# Prototype_Schematic.net
KiCad netlist of a schematic drawn in EAGLE
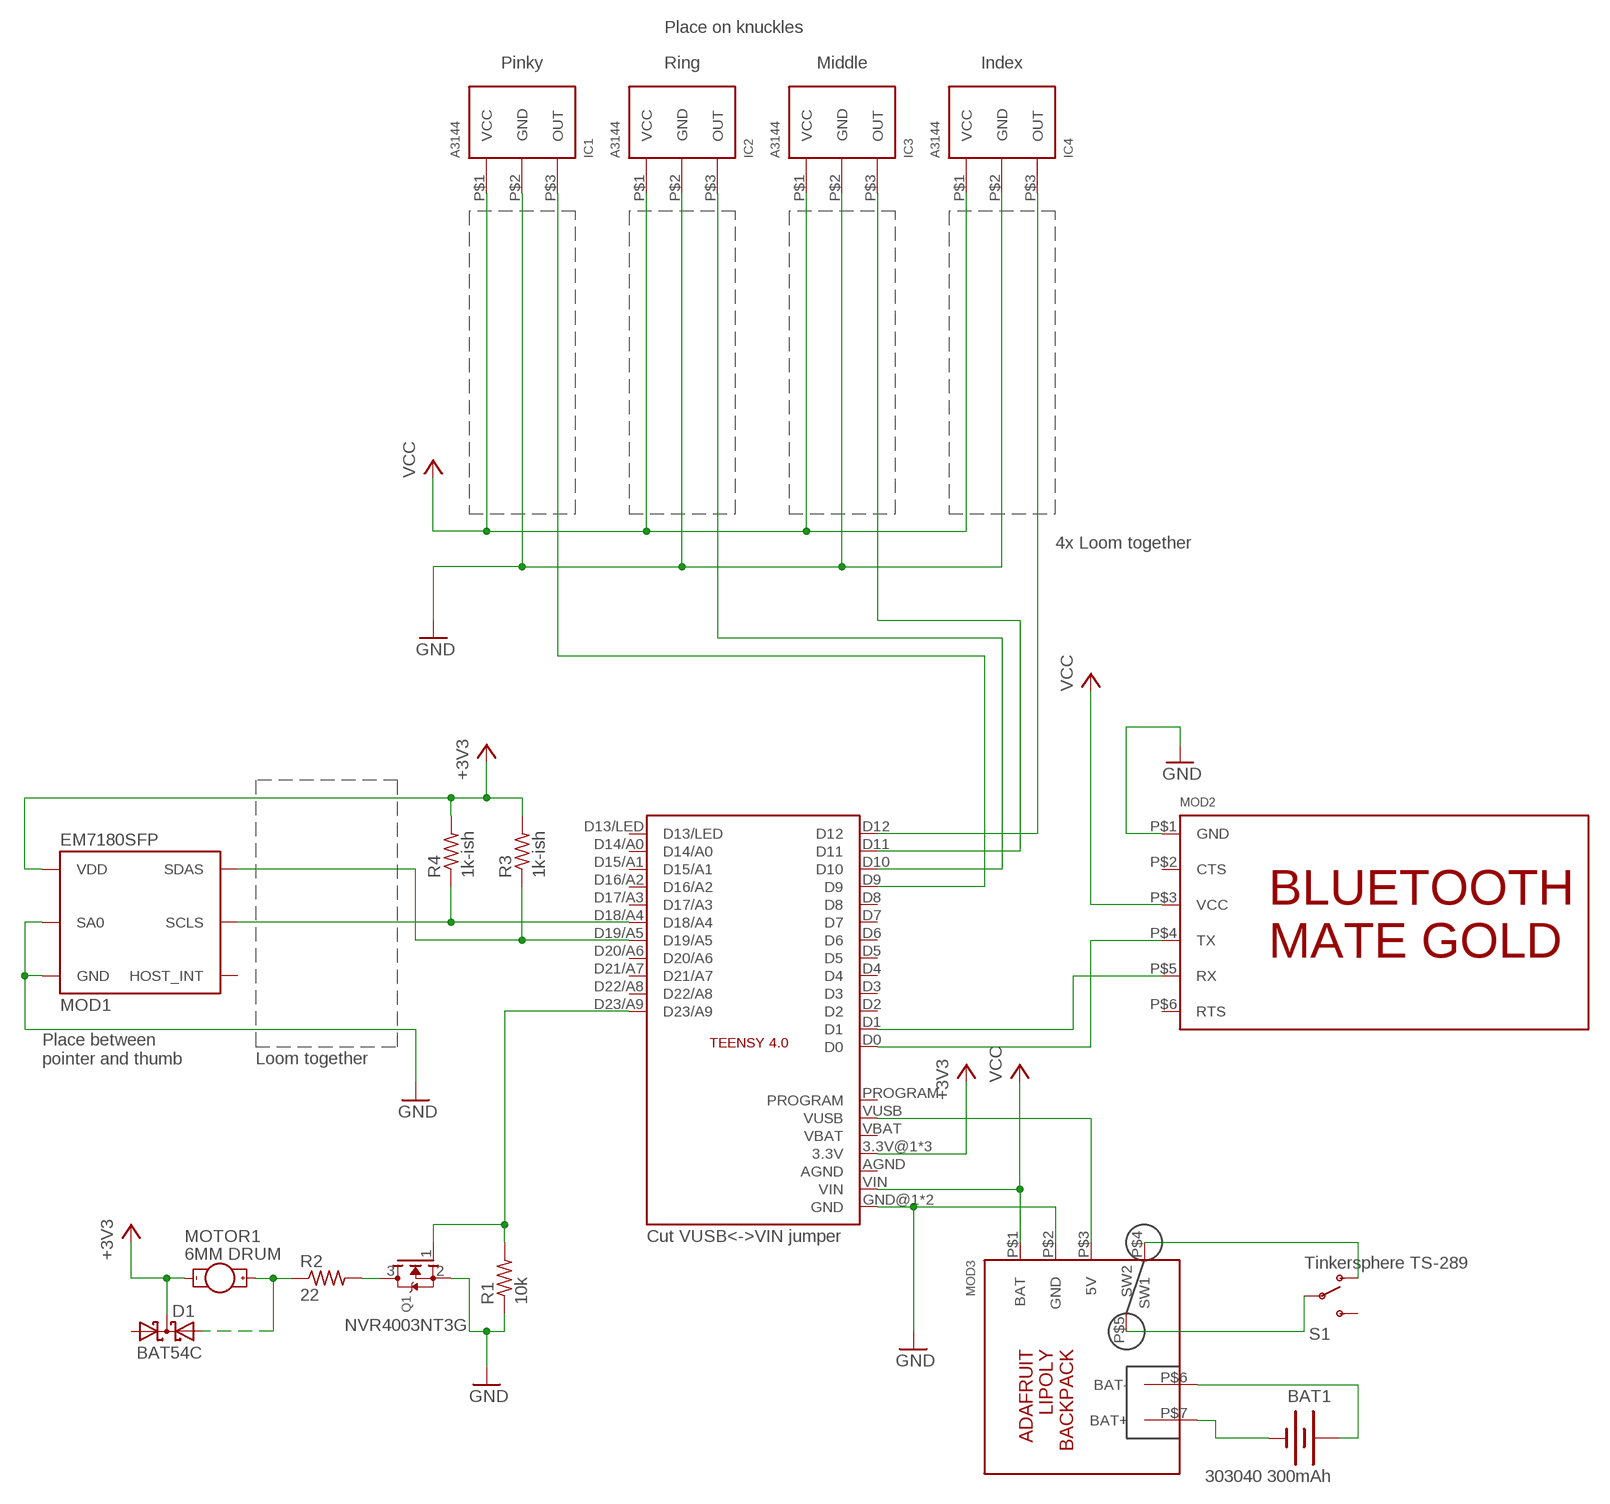
[diagram p0: schematic, sheet 1]

(export (version "E")
  (design (tool "Eeschema 10.0.6"))
  (components
    (comp (ref "BAT1")
      (value "303040 300mAh")
      (footprint "eagle-import:LIPO-110-TABS")
      (libsource (lib "eagle-import") (part "BATTERYLIPO-TABS"))
    )
    (comp (ref "D1")
      (value "BAT54C")
      (footprint "eagle-import:SOT23")
      (libsource (lib "eagle-import") (part "BAT54C"))
    )
    (comp (ref "IC1")
      (value "A3144")
      (footprint "eagle-import:DUMMY-PIN")
      (libsource (lib "eagle-import") (part "A314"))
    )
    (comp (ref "IC2")
      (value "A3144")
      (footprint "eagle-import:DUMMY-PIN")
      (libsource (lib "eagle-import") (part "A314"))
    )
    (comp (ref "IC3")
      (value "A3144")
      (footprint "eagle-import:DUMMY-PIN")
      (libsource (lib "eagle-import") (part "A314"))
    )
    (comp (ref "IC4")
      (value "A3144")
      (footprint "eagle-import:DUMMY-PIN")
      (libsource (lib "eagle-import") (part "A314"))
    )
    (comp (ref "MOD1")
      (value "EM7180SFP")
      (footprint "eagle-import:EM7180SFP")
      (libsource (lib "eagle-import") (part "EM7180SFP"))
    )
    (comp (ref "MOD2")
      (value "BLUETOOTH-MATE-GOLD")
      (footprint "eagle-import:DUMMY-PIN")
      (libsource (lib "eagle-import") (part "BLUETOOTH-MATE-GOLD"))
    )
    (comp (ref "MOD3")
      (value "LIPOLY-BACKPACK")
      (footprint "eagle-import:DUMMY-PIN")
      (libsource (lib "eagle-import") (part "LIPOLY-BACKPACK"))
    )
    (comp (ref "MOTOR1")
      (value "6MM DRUM")
      (footprint "eagle-import:VIBE-MOTOR-10MM")
      (libsource (lib "eagle-import") (part "MOTOR10MM"))
    )
    (comp (ref "Q1")
      (value "MOSFET-NREFLOW")
      (footprint "eagle-import:SOT23")
      (libsource (lib "eagle-import") (part "MOSFET-NREFLOW"))
    )
    (comp (ref "R1")
      (value "10k")
      (footprint "eagle-import:R0603")
      (libsource (lib "eagle-import") (part "R-US_R0603"))
    )
    (comp (ref "R2")
      (value "22")
      (footprint "eagle-import:R0603")
      (libsource (lib "eagle-import") (part "R-US_R0603"))
    )
    (comp (ref "R3")
      (value "1k-ish")
      (footprint "eagle-import:R0603")
      (libsource (lib "eagle-import") (part "R-US_R0603"))
    )
    (comp (ref "R4")
      (value "1k-ish")
      (footprint "eagle-import:R0603")
      (libsource (lib "eagle-import") (part "R-US_R0603"))
    )
    (comp (ref "S1")
      (value "Tinkersphere TS-289")
      (footprint "eagle-import:SWITCH-SPDT")
      (libsource (lib "eagle-import") (part "SWITCH-SPDTPTH"))
    )
    (comp (ref "U$1")
      (value "TEENSY4.0")
      (footprint "eagle-import:TEENSY4.0")
      (libsource (lib "eagle-import") (part "TEENSY4.0"))
    )
  )
  (nets
    (net (code "1") (name "+3V3") (class "Default")
      (node (ref "D1") (pin "3") (pinfunction "CC_3") (pintype "passive"))
      (node (ref "MOD1") (pin "P$1") (pinfunction "VDD_P$1") (pintype "bidirectional"))
      (node (ref "MOTOR1") (pin "-") (pinfunction "-_-") (pintype "bidirectional"))
      (node (ref "R3") (pin "2") (pinfunction "2_2") (pintype "passive"))
      (node (ref "R4") (pin "2") (pinfunction "2_2") (pintype "passive"))
      (node (ref "U$1") (pin "3.3V@1") (pinfunction "3.3V_3.3V@1") (pintype "bidirectional"))
      (node (ref "U$1") (pin "3.3V@2") (pinfunction "3.3V_3.3V@2") (pintype "bidirectional"))
      (node (ref "U$1") (pin "ON/OFF") (pinfunction "3.3V_ON/OFF") (pintype "bidirectional"))
    )
    (net (code "2") (name "GND") (class "Default")
      (node (ref "IC1") (pin "P$2") (pinfunction "GND_P$2") (pintype "bidirectional"))
      (node (ref "IC2") (pin "P$2") (pinfunction "GND_P$2") (pintype "bidirectional"))
      (node (ref "IC3") (pin "P$2") (pinfunction "GND_P$2") (pintype "bidirectional"))
      (node (ref "IC4") (pin "P$2") (pinfunction "GND_P$2") (pintype "bidirectional"))
      (node (ref "MOD1") (pin "P$5") (pinfunction "SA0_P$5") (pintype "bidirectional"))
      (node (ref "MOD1") (pin "P$6") (pinfunction "GND_P$6") (pintype "bidirectional"))
      (node (ref "MOD2") (pin "P$1") (pinfunction "GND_P$1") (pintype "bidirectional"))
      (node (ref "MOD3") (pin "P$2") (pinfunction "GND_P$2") (pintype "bidirectional"))
      (node (ref "Q1") (pin "2") (pinfunction "S_2") (pintype "bidirectional"))
      (node (ref "R1") (pin "1") (pinfunction "1_1") (pintype "passive"))
      (node (ref "U$1") (pin "GND@1") (pinfunction "GND_GND@1") (pintype "bidirectional"))
      (node (ref "U$1") (pin "GND@2") (pinfunction "GND_GND@2") (pintype "bidirectional"))
    )
    (net (code "3") (name "Net-(D1-A2)") (class "Default")
      (node (ref "D1") (pin "2") (pinfunction "A2_2") (pintype "passive"))
      (node (ref "MOTOR1") (pin "+") (pinfunction "+_+") (pintype "bidirectional"))
      (node (ref "R2") (pin "1") (pinfunction "1_1") (pintype "passive"))
    )
    (net (code "4") (name "Net-(IC1-OUT)") (class "Default")
      (node (ref "IC1") (pin "P$3") (pinfunction "OUT_P$3") (pintype "bidirectional"))
      (node (ref "U$1") (pin "D9") (pinfunction "D9_D9") (pintype "bidirectional"))
    )
    (net (code "5") (name "Net-(IC2-OUT)") (class "Default")
      (node (ref "IC2") (pin "P$3") (pinfunction "OUT_P$3") (pintype "bidirectional"))
      (node (ref "U$1") (pin "D10") (pinfunction "D10_D10") (pintype "bidirectional"))
    )
    (net (code "6") (name "Net-(IC3-OUT)") (class "Default")
      (node (ref "IC3") (pin "P$3") (pinfunction "OUT_P$3") (pintype "bidirectional"))
      (node (ref "U$1") (pin "D11") (pinfunction "D11_D11") (pintype "bidirectional"))
    )
    (net (code "7") (name "Net-(IC4-OUT)") (class "Default")
      (node (ref "IC4") (pin "P$3") (pinfunction "OUT_P$3") (pintype "bidirectional"))
      (node (ref "U$1") (pin "D12") (pinfunction "D12_D12") (pintype "bidirectional"))
    )
    (net (code "8") (name "Net-(MOD1-SCLS)") (class "Default")
      (node (ref "MOD1") (pin "P$3") (pinfunction "SCLS_P$3") (pintype "bidirectional"))
      (node (ref "R4") (pin "1") (pinfunction "1_1") (pintype "passive"))
      (node (ref "U$1") (pin "D18/A4") (pinfunction "D18/A4_D18/A4") (pintype "bidirectional"))
    )
    (net (code "9") (name "Net-(MOD1-SDAS)") (class "Default")
      (node (ref "MOD1") (pin "P$2") (pinfunction "SDAS_P$2") (pintype "bidirectional"))
      (node (ref "R3") (pin "1") (pinfunction "1_1") (pintype "passive"))
      (node (ref "U$1") (pin "D19/A5") (pinfunction "D19/A5_D19/A5") (pintype "bidirectional"))
    )
    (net (code "10") (name "Net-(MOD2-RX)") (class "Default")
      (node (ref "MOD2") (pin "P$5") (pinfunction "RX_P$5") (pintype "bidirectional"))
      (node (ref "U$1") (pin "D1") (pinfunction "D1_D1") (pintype "bidirectional"))
    )
    (net (code "11") (name "Net-(MOD2-TX)") (class "Default")
      (node (ref "MOD2") (pin "P$4") (pinfunction "TX_P$4") (pintype "bidirectional"))
      (node (ref "U$1") (pin "D0") (pinfunction "D0_D0") (pintype "bidirectional"))
    )
    (net (code "12") (name "Net-(MOD3-5V)") (class "Default")
      (node (ref "MOD3") (pin "P$3") (pinfunction "5V_P$3") (pintype "bidirectional"))
      (node (ref "U$1") (pin "VUSB") (pinfunction "VUSB_VUSB") (pintype "bidirectional"))
    )
    (net (code "13") (name "Net-(MOD3-BAT+)") (class "Default")
      (node (ref "BAT1") (pin "-") (pinfunction "-_-") (pintype "power_in"))
      (node (ref "MOD3") (pin "P$7") (pinfunction "BAT+_P$7") (pintype "bidirectional"))
    )
    (net (code "14") (name "Net-(MOD3-BAT-)") (class "Default")
      (node (ref "BAT1") (pin "+") (pinfunction "+_+") (pintype "power_in"))
      (node (ref "MOD3") (pin "P$6") (pinfunction "BAT-_P$6") (pintype "bidirectional"))
    )
    (net (code "15") (name "Net-(MOD3-SW1)") (class "Default")
      (node (ref "MOD3") (pin "P$4") (pinfunction "SW1_P$4") (pintype "bidirectional"))
      (node (ref "S1") (pin "1") (pinfunction "O_1") (pintype "passive"))
    )
    (net (code "16") (name "Net-(MOD3-SW2)") (class "Default")
      (node (ref "MOD3") (pin "P$5") (pinfunction "SW2_P$5") (pintype "bidirectional"))
      (node (ref "S1") (pin "2") (pinfunction "P_2") (pintype "passive"))
    )
    (net (code "17") (name "Net-(Q1-D)") (class "Default")
      (node (ref "Q1") (pin "3") (pinfunction "D_3") (pintype "bidirectional"))
      (node (ref "R2") (pin "2") (pinfunction "2_2") (pintype "passive"))
    )
    (net (code "18") (name "Net-(Q1-G)") (class "Default")
      (node (ref "Q1") (pin "1") (pinfunction "G_1") (pintype "bidirectional"))
      (node (ref "R1") (pin "2") (pinfunction "2_2") (pintype "passive"))
      (node (ref "U$1") (pin "D23/A9") (pinfunction "D23/A9_D23/A9") (pintype "bidirectional"))
    )
    (net (code "19") (name "VCC") (class "Default")
      (node (ref "IC1") (pin "P$1") (pinfunction "VCC_P$1") (pintype "bidirectional"))
      (node (ref "IC2") (pin "P$1") (pinfunction "VCC_P$1") (pintype "bidirectional"))
      (node (ref "IC3") (pin "P$1") (pinfunction "VCC_P$1") (pintype "bidirectional"))
      (node (ref "IC4") (pin "P$1") (pinfunction "VCC_P$1") (pintype "bidirectional"))
      (node (ref "MOD2") (pin "P$3") (pinfunction "VCC_P$3") (pintype "bidirectional"))
      (node (ref "MOD3") (pin "P$1") (pinfunction "BAT_P$1") (pintype "bidirectional"))
      (node (ref "U$1") (pin "VIN") (pinfunction "VIN_VIN") (pintype "bidirectional"))
    )
    (net (code "20") (name "unconnected-(D1-A1-Pad1)") (class "Default")
      (node (ref "D1") (pin "1") (pinfunction "A1_1") (pintype "passive"))
    )
    (net (code "21") (name "unconnected-(MOD1-HOST_INT-PadP$4)") (class "Default")
      (node (ref "MOD1") (pin "P$4") (pinfunction "HOST_INT_P$4") (pintype "bidirectional"))
    )
    (net (code "22") (name "unconnected-(MOD2-CTS-PadP$2)") (class "Default")
      (node (ref "MOD2") (pin "P$2") (pinfunction "CTS_P$2") (pintype "bidirectional"))
    )
    (net (code "23") (name "unconnected-(MOD2-RTS-PadP$6)") (class "Default")
      (node (ref "MOD2") (pin "P$6") (pinfunction "RTS_P$6") (pintype "bidirectional"))
    )
    (net (code "24") (name "unconnected-(S1-S-Pad3)") (class "Default")
      (node (ref "S1") (pin "3") (pinfunction "S_3") (pintype "passive"))
    )
    (net (code "25") (name "unconnected-(U$1-PadAGND)") (class "Default")
      (node (ref "U$1") (pin "AGND") (pinfunction "AGND_AGND") (pintype "bidirectional"))
    )
    (net (code "26") (name "unconnected-(U$1-PadD2)") (class "Default")
      (node (ref "U$1") (pin "D2") (pinfunction "D2_D2") (pintype "bidirectional"))
    )
    (net (code "27") (name "unconnected-(U$1-PadD3)") (class "Default")
      (node (ref "U$1") (pin "D3") (pinfunction "D3_D3") (pintype "bidirectional"))
    )
    (net (code "28") (name "unconnected-(U$1-PadD4)") (class "Default")
      (node (ref "U$1") (pin "D4") (pinfunction "D4_D4") (pintype "bidirectional"))
    )
    (net (code "29") (name "unconnected-(U$1-PadD5)") (class "Default")
      (node (ref "U$1") (pin "D5") (pinfunction "D5_D5") (pintype "bidirectional"))
    )
    (net (code "30") (name "unconnected-(U$1-PadD6)") (class "Default")
      (node (ref "U$1") (pin "D6") (pinfunction "D6_D6") (pintype "bidirectional"))
    )
    (net (code "31") (name "unconnected-(U$1-PadD7)") (class "Default")
      (node (ref "U$1") (pin "D7") (pinfunction "D7_D7") (pintype "bidirectional"))
    )
    (net (code "32") (name "unconnected-(U$1-PadD8)") (class "Default")
      (node (ref "U$1") (pin "D8") (pinfunction "D8_D8") (pintype "bidirectional"))
    )
    (net (code "33") (name "unconnected-(U$1-PadD13{slash}LED)") (class "Default")
      (node (ref "U$1") (pin "D13/LED") (pinfunction "D13/LED_D13/LED") (pintype "bidirectional"))
    )
    (net (code "34") (name "unconnected-(U$1-PadD14{slash}A0)") (class "Default")
      (node (ref "U$1") (pin "D14/A0") (pinfunction "D14/A0_D14/A0") (pintype "bidirectional"))
    )
    (net (code "35") (name "unconnected-(U$1-PadD15{slash}A1)") (class "Default")
      (node (ref "U$1") (pin "D15/A1") (pinfunction "D15/A1_D15/A1") (pintype "bidirectional"))
    )
    (net (code "36") (name "unconnected-(U$1-PadD16{slash}A2)") (class "Default")
      (node (ref "U$1") (pin "D16/A2") (pinfunction "D16/A2_D16/A2") (pintype "bidirectional"))
    )
    (net (code "37") (name "unconnected-(U$1-PadD17{slash}A3)") (class "Default")
      (node (ref "U$1") (pin "D17/A3") (pinfunction "D17/A3_D17/A3") (pintype "bidirectional"))
    )
    (net (code "38") (name "unconnected-(U$1-PadD20{slash}A6)") (class "Default")
      (node (ref "U$1") (pin "D20/A6") (pinfunction "D20/A6_D20/A6") (pintype "bidirectional"))
    )
    (net (code "39") (name "unconnected-(U$1-PadD21{slash}A7)") (class "Default")
      (node (ref "U$1") (pin "D21/A7") (pinfunction "D21/A7_D21/A7") (pintype "bidirectional"))
    )
    (net (code "40") (name "unconnected-(U$1-PadD22{slash}A8)") (class "Default")
      (node (ref "U$1") (pin "D22/A8") (pinfunction "D22/A8_D22/A8") (pintype "bidirectional"))
    )
    (net (code "41") (name "unconnected-(U$1-PadPROGRAM)") (class "Default")
      (node (ref "U$1") (pin "PROGRAM") (pinfunction "PROGRAM_PROGRAM") (pintype "bidirectional"))
    )
    (net (code "42") (name "unconnected-(U$1-PadVBAT)") (class "Default")
      (node (ref "U$1") (pin "VBAT") (pinfunction "VBAT_VBAT") (pintype "bidirectional"))
    )
  )
)
